# TIDA-010933-DCDC-Top.net
KiCad netlist of a schematic drawn in Altium Designer
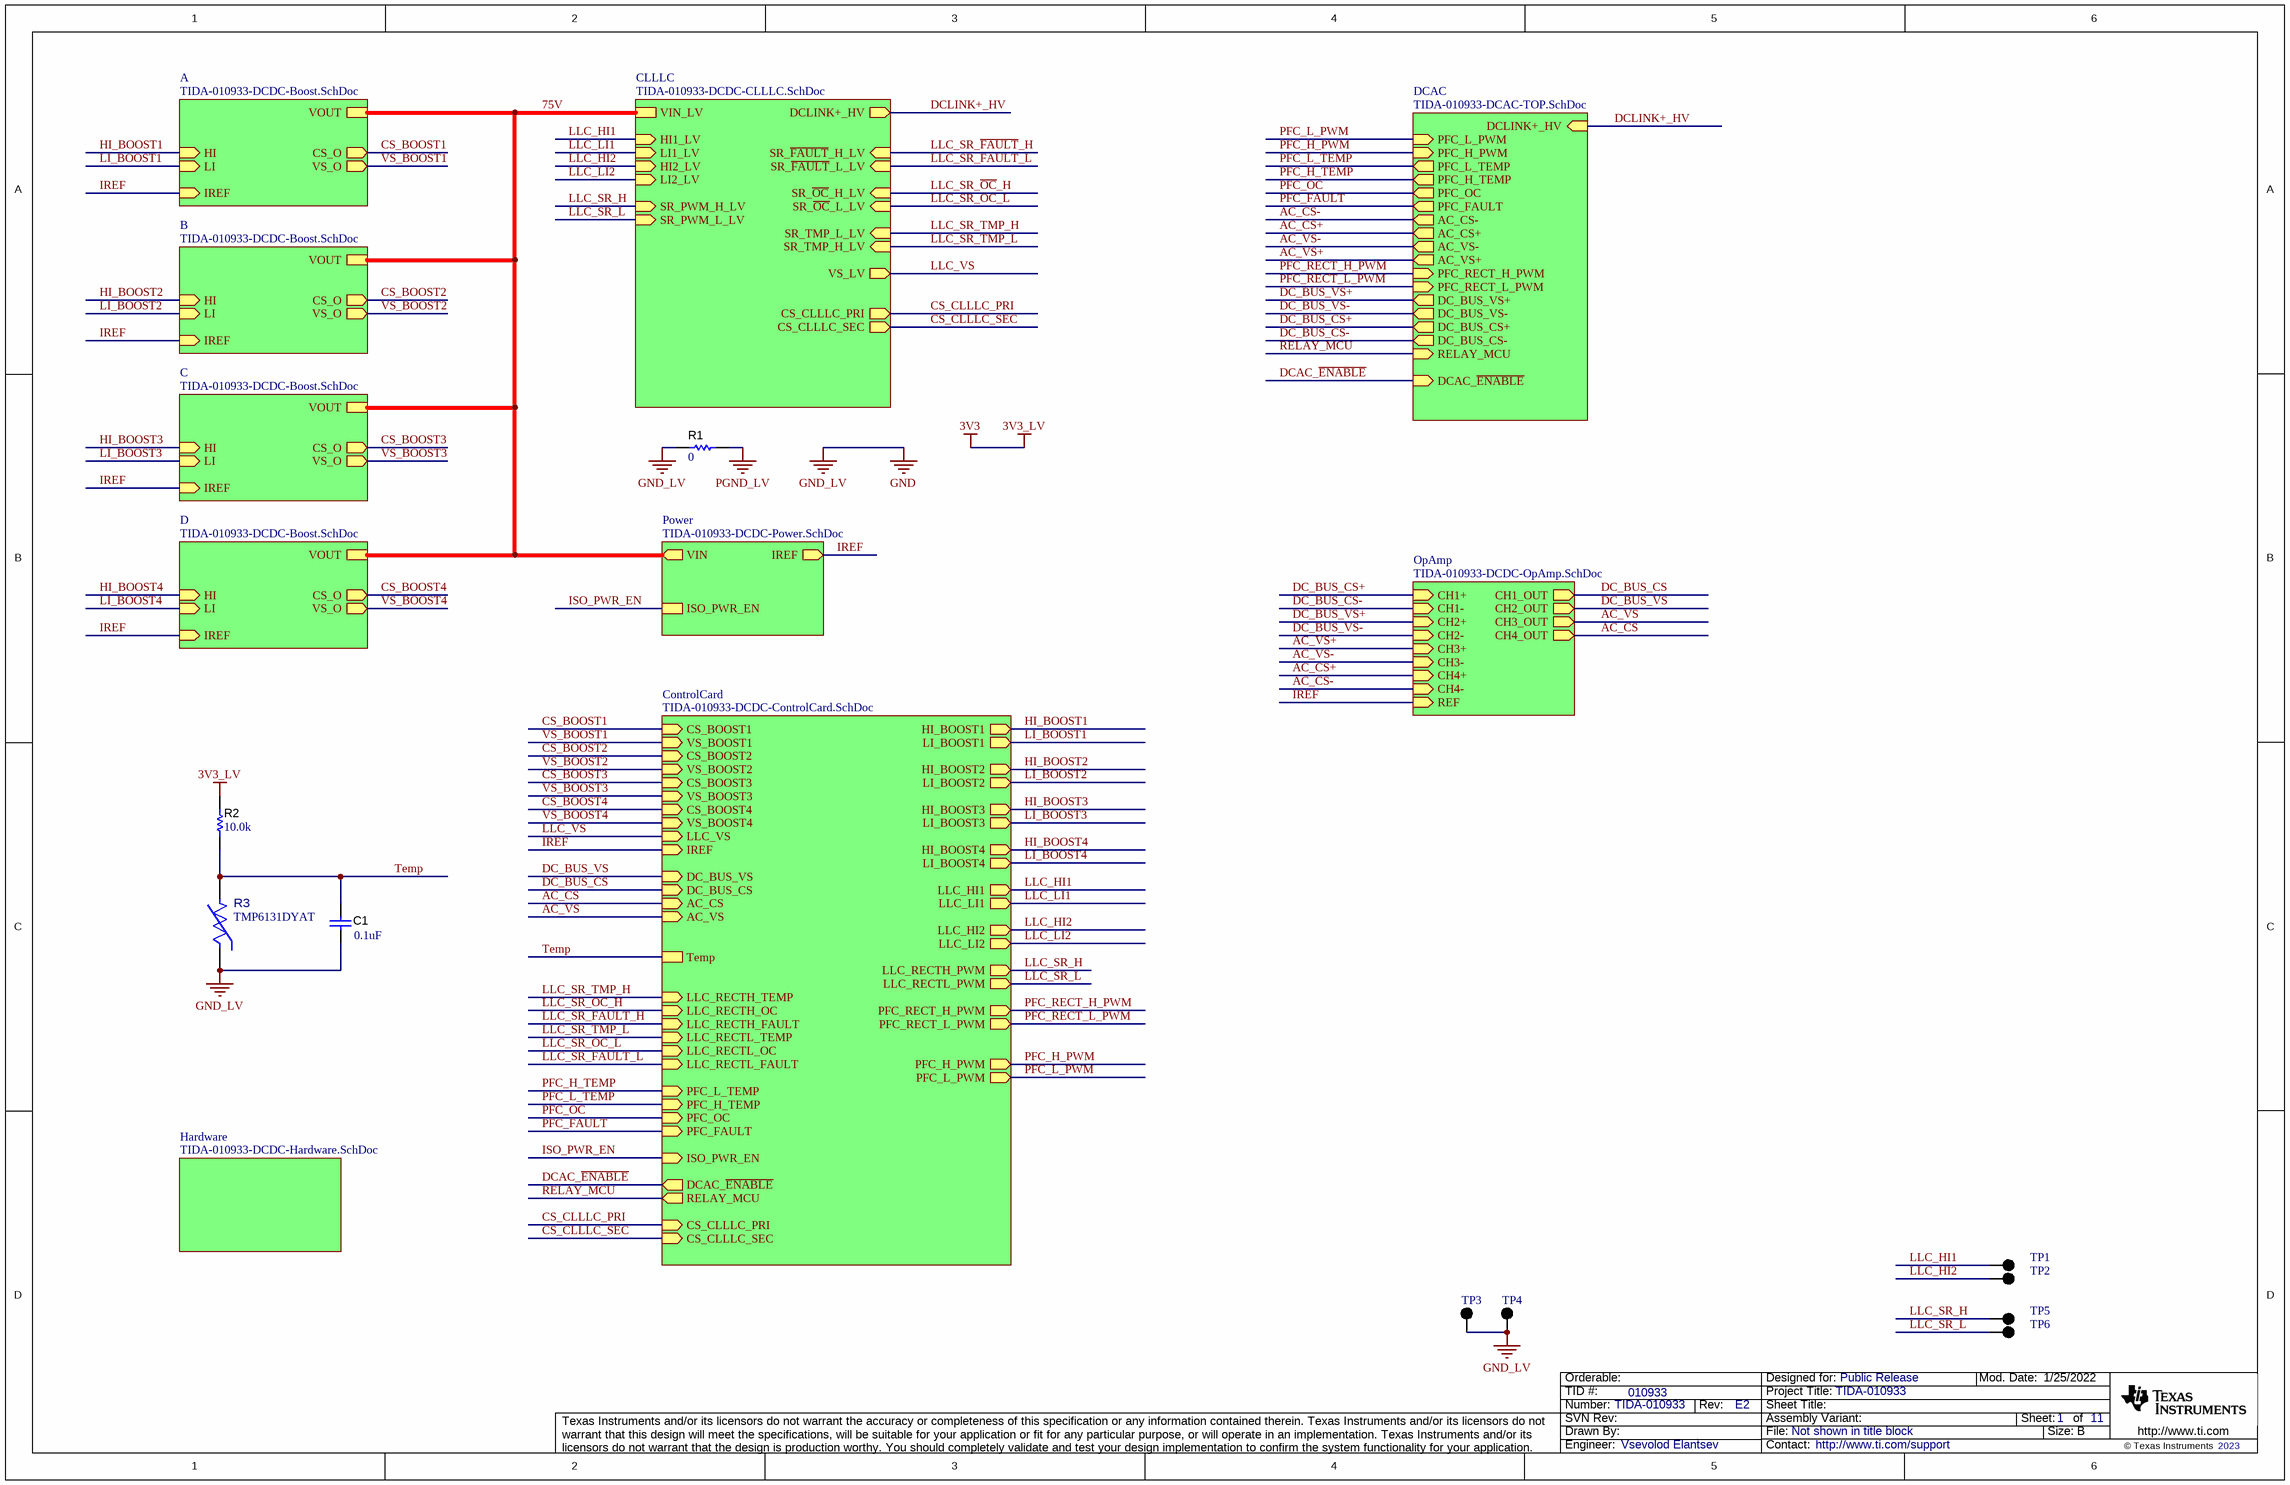
[diagram p0: TIDA-010933-DCDC-Top.SchDoc]

(export (version "E")
  (design (tool "Eeschema 10.0.6"))
  (components
    (comp (ref "C1")
      (value "GRM155R71E104KE14D")
      (footprint "0402")
      (description "CAP, CERM, 0.1 uF, 25 V, +/- 10%, X7R, 0402")
      (fields
        (field (name "MANUFACTURER") "MuRata")
        (field (name "VALUEDISPLAYED") "0.1uF")
        (field (name "PUBLISHER") "Texas Instruments")
      )
      (libsource (lib "Altium Vault - TI") (part "Capacitor"))
    )
    (comp (ref "R1")
      (value "RC0603JR-070RL")
      (footprint "0603")
      (description "RES, 0, 5%, 0.1 W, 0603")
      (fields (field (name "MANUFACTURER") "Yageo") (field (name "VALUEDISPLAYED") "0"))
      (libsource (lib "Altium Vault - TI") (part "Resistor"))
    )
    (comp (ref "R2")
      (value "RT0402BRD0710KL")
      (footprint "0402")
      (description "RES, 10.0 k, .1%, .0625 W, 0402")
      (fields
        (field (name "MANUFACTURER") "Yageo America")
        (field (name "VALUEDISPLAYED") "10.0k")
        (field (name "PUBLISHER") "Texas Instruments")
      )
      (libsource (lib "Altium Vault - TI") (part "Resistor"))
    )
    (comp (ref "R3")
      (value "TMP6131DYAT")
      (footprint "DYA0002A-MFG")
      (fields
        (field (name "MANUFACTURER") "Texas Instruments")
        (field (name "DIGIKEY PART NUMBER") "296-TMP6131DYATCT-ND")
        (field (name "MOUSER PART NUMBER") "595-TMP6131DYAT")
        (field (name "PARTNUMBER") "TMP6131DYAT")
      )
      (libsource (lib "Altium Vault - TI") (part "SYM-TMP6131DYAT"))
    )
    (comp (ref "TP1")
      (value "5001")
      (footprint "Keystone5001")
      (description "Test Point, Miniature, Black, TH")
      (fields
        (field (name "MANUFACTURER") "Keystone Electronics")
        (field (name "PUBLISHER") "Texas Instruments")
      )
      (libsource (lib "Altium Vault - TI") (part "5001"))
    )
    (comp (ref "TP2")
      (value "5001")
      (footprint "Keystone5001")
      (description "Test Point, Miniature, Black, TH")
      (fields
        (field (name "MANUFACTURER") "Keystone Electronics")
        (field (name "PUBLISHER") "Texas Instruments")
      )
      (libsource (lib "Altium Vault - TI") (part "5001"))
    )
    (comp (ref "TP3")
      (value "5001")
      (footprint "Keystone5001")
      (description "Test Point, Miniature, Black, TH")
      (fields
        (field (name "MANUFACTURER") "Keystone Electronics")
        (field (name "PUBLISHER") "Texas Instruments")
      )
      (libsource (lib "Altium Vault - TI") (part "5001"))
    )
    (comp (ref "TP4")
      (value "5001")
      (footprint "Keystone5001")
      (description "Test Point, Miniature, Black, TH")
      (fields
        (field (name "MANUFACTURER") "Keystone Electronics")
        (field (name "PUBLISHER") "Texas Instruments")
      )
      (libsource (lib "Altium Vault - TI") (part "5001"))
    )
    (comp (ref "TP5")
      (value "5001")
      (footprint "Keystone5001")
      (description "Test Point, Miniature, Black, TH")
      (fields
        (field (name "MANUFACTURER") "Keystone Electronics")
        (field (name "PUBLISHER") "Texas Instruments")
      )
      (libsource (lib "Altium Vault - TI") (part "5001"))
    )
    (comp (ref "TP6")
      (value "5001")
      (footprint "Keystone5001")
      (description "Test Point, Miniature, Black, TH")
      (fields
        (field (name "MANUFACTURER") "Keystone Electronics")
        (field (name "PUBLISHER") "Texas Instruments")
      )
      (libsource (lib "Altium Vault - TI") (part "5001"))
    )
  )
  (nets
    (net (code "32") (name "/LLC_HI1") (class "Default") (node (ref "TP1") (pin "1") (pintype "passive")))
    (net (code "33") (name "/LLC_HI2") (class "Default") (node (ref "TP2") (pin "1") (pintype "passive")))
    (net (code "36") (name "/LLC_SR_H") (class "Default") (node (ref "TP5") (pin "1") (pintype "passive")))
    (net (code "37") (name "/LLC_SR_L") (class "Default") (node (ref "TP6") (pin "1") (pintype "passive")))
    (net (code "54") (name "/Temp") (class "Default")
      (node (ref "C1") (pin "1") (pinfunction "1_1") (pintype "passive"))
      (node (ref "R2") (pin "1") (pinfunction "1_1") (pintype "passive"))
      (node (ref "R3") (pin "1") (pinfunction "-_1") (pintype "passive"))
    )
    (net (code "59") (name "3V3") (class "Default")
      (node (ref "R2") (pin "2") (pinfunction "2_2") (pintype "passive"))
    )
    (net (code "60") (name "GND") (class "Default")
      (node (ref "C1") (pin "2") (pinfunction "2_2") (pintype "passive"))
      (node (ref "R1") (pin "1") (pinfunction "1_1") (pintype "passive"))
      (node (ref "R3") (pin "2") (pinfunction "+_2") (pintype "passive"))
      (node (ref "TP3") (pin "1") (pintype "passive"))
      (node (ref "TP4") (pin "1") (pintype "passive"))
    )
    (net (code "61") (name "PGND_LV") (class "Default")
      (node (ref "R1") (pin "2") (pinfunction "2_2") (pintype "passive"))
    )
  )
)
